# SparkFun_DC-DC_Converter_Breakout.net
KiCad netlist of a schematic drawn in EAGLE
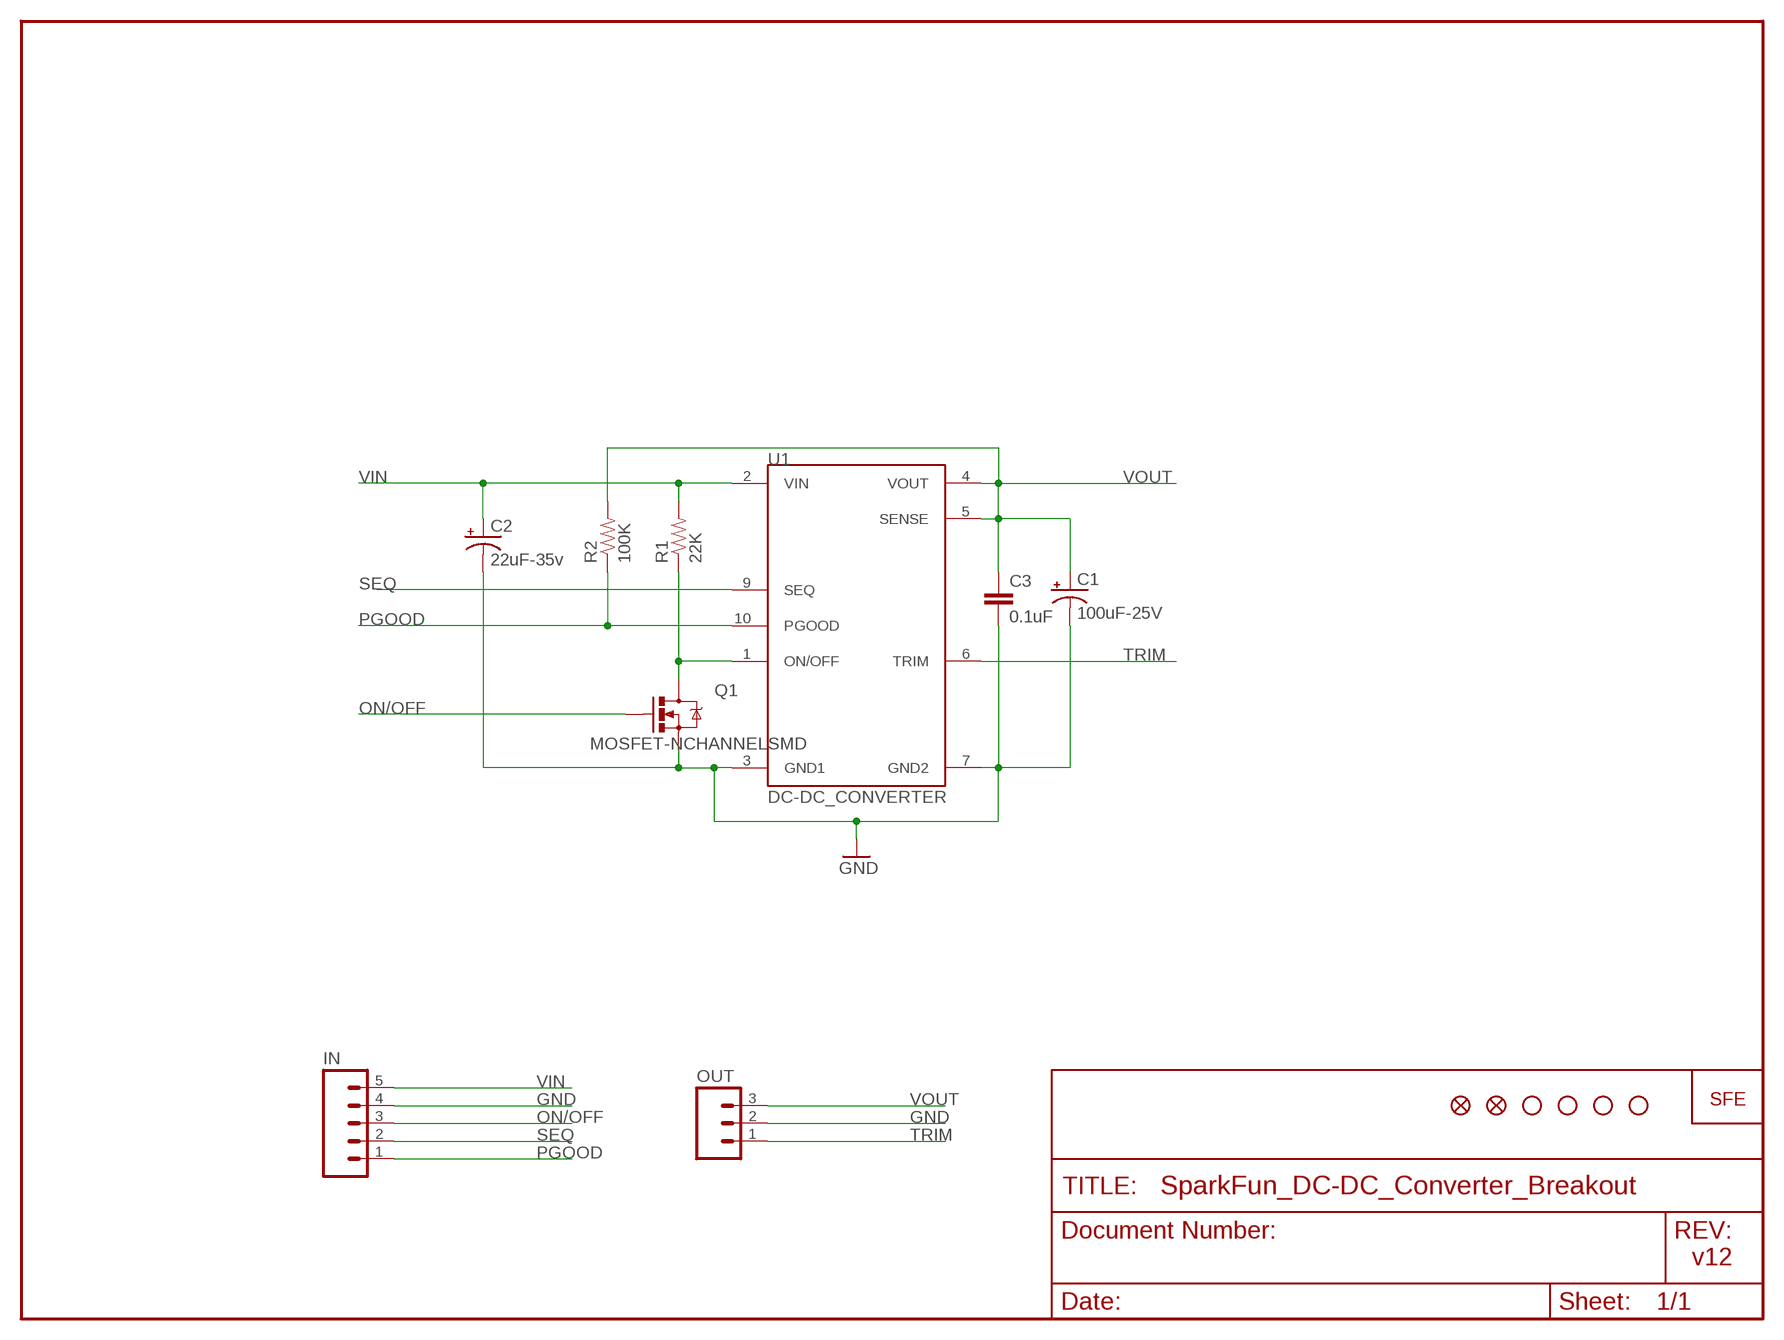
[diagram p0: schematic, sheet 1]

(export (version "E")
  (design (tool "Eeschema 10.0.6"))
  (components
    (comp (ref "C1")
      (value "100uF-25V")
      (footprint "eagle-import:NIPPON_F80")
      (libsource (lib "eagle-import") (part "CAP_POL"))
    )
    (comp (ref "C2")
      (value "22uF-35v")
      (footprint "eagle-import:PANASONIC_C")
      (libsource (lib "eagle-import") (part "CAP_POLC"))
    )
    (comp (ref "C3")
      (value "0.1uF")
      (footprint "eagle-import:0603-CAP")
      (libsource (lib "eagle-import") (part "CAP0603-CAP"))
    )
    (comp (ref "FID1")
      (value "FIDUCIAL1X2")
      (footprint "eagle-import:FIDUCIAL-1X2")
      (libsource (lib "eagle-import") (part "FIDUCIAL1X2"))
    )
    (comp (ref "FID2")
      (value "FIDUCIAL1X2")
      (footprint "eagle-import:FIDUCIAL-1X2")
      (libsource (lib "eagle-import") (part "FIDUCIAL1X2"))
    )
    (comp (ref "IN")
      (value "M05PTH")
      (footprint "eagle-import:1X05")
      (libsource (lib "eagle-import") (part "M05PTH"))
    )
    (comp (ref "OUT")
      (value "M03PTH")
      (footprint "eagle-import:1X03")
      (libsource (lib "eagle-import") (part "M03PTH"))
    )
    (comp (ref "Q1")
      (value "MOSFET-NCHANNELSMD")
      (footprint "eagle-import:SOT23-3")
      (libsource (lib "eagle-import") (part "MOSFET-NCHANNELSMD"))
    )
    (comp (ref "R1")
      (value "22K")
      (footprint "eagle-import:0603-RES")
      (libsource (lib "eagle-import") (part "RESISTOR0603-RES"))
    )
    (comp (ref "R2")
      (value "100K")
      (footprint "eagle-import:0603-RES")
      (libsource (lib "eagle-import") (part "RESISTOR0603-RES"))
    )
    (comp (ref "U$1")
      (value "STAND-OFF")
      (footprint "eagle-import:STAND-OFF")
      (libsource (lib "eagle-import") (part "STAND-OFF"))
    )
    (comp (ref "U$2")
      (value "LOGO-SFENEW")
      (footprint "eagle-import:SFE-NEW-WEBLOGO")
      (libsource (lib "eagle-import") (part "LOGO-SFENEW"))
    )
    (comp (ref "U$3")
      (value "STAND-OFF")
      (footprint "eagle-import:STAND-OFF")
      (libsource (lib "eagle-import") (part "STAND-OFF"))
    )
    (comp (ref "U$4")
      (value "STAND-OFF")
      (footprint "eagle-import:STAND-OFF")
      (libsource (lib "eagle-import") (part "STAND-OFF"))
    )
    (comp (ref "U$5")
      (value "STAND-OFF")
      (footprint "eagle-import:STAND-OFF")
      (libsource (lib "eagle-import") (part "STAND-OFF"))
    )
    (comp (ref "U1")
      (value "DC-DC_CONVERTER")
      (footprint "eagle-import:DC-DC_CONVERTER")
      (libsource (lib "eagle-import") (part "DC-DC_CONVERTER"))
    )
  )
  (nets
    (net (code "1") (name "/ON{slash}OFF") (class "Default")
      (node (ref "IN") (pin "3") (pinfunction "3_3") (pintype "passive"))
      (node (ref "Q1") (pin "1") (pinfunction "G_1") (pintype "passive"))
    )
    (net (code "2") (name "/PGOOD") (class "Default")
      (node (ref "IN") (pin "1") (pinfunction "1_1") (pintype "passive"))
      (node (ref "R2") (pin "1") (pinfunction "1_1") (pintype "passive"))
      (node (ref "U1") (pin "10") (pinfunction "PGOOD_10") (pintype "bidirectional"))
    )
    (net (code "3") (name "/SEQ") (class "Default")
      (node (ref "IN") (pin "2") (pinfunction "2_2") (pintype "passive"))
      (node (ref "U1") (pin "9") (pinfunction "SEQ_9") (pintype "bidirectional"))
    )
    (net (code "4") (name "/TRIM") (class "Default")
      (node (ref "OUT") (pin "1") (pinfunction "1_1") (pintype "passive"))
      (node (ref "U1") (pin "6") (pinfunction "TRIM_6") (pintype "bidirectional"))
    )
    (net (code "5") (name "/VIN") (class "Default")
      (node (ref "C2") (pin "+") (pinfunction "+_+") (pintype "passive"))
      (node (ref "IN") (pin "5") (pinfunction "5_5") (pintype "passive"))
      (node (ref "R1") (pin "2") (pinfunction "2_2") (pintype "passive"))
      (node (ref "U1") (pin "2") (pinfunction "VIN_2") (pintype "bidirectional"))
    )
    (net (code "6") (name "/VOUT") (class "Default")
      (node (ref "C1") (pin "+") (pinfunction "+_+") (pintype "passive"))
      (node (ref "C3") (pin "1") (pinfunction "1_1") (pintype "passive"))
      (node (ref "OUT") (pin "3") (pinfunction "3_3") (pintype "passive"))
      (node (ref "R2") (pin "2") (pinfunction "2_2") (pintype "passive"))
      (node (ref "U1") (pin "4") (pinfunction "VOUT_4") (pintype "bidirectional"))
      (node (ref "U1") (pin "5") (pinfunction "SENSE_5") (pintype "bidirectional"))
    )
    (net (code "7") (name "GND") (class "Default")
      (node (ref "C1") (pin "-") (pinfunction "-_-") (pintype "passive"))
      (node (ref "C2") (pin "-") (pinfunction "-_-") (pintype "passive"))
      (node (ref "C3") (pin "2") (pinfunction "2_2") (pintype "passive"))
      (node (ref "IN") (pin "4") (pinfunction "4_4") (pintype "passive"))
      (node (ref "OUT") (pin "2") (pinfunction "2_2") (pintype "passive"))
      (node (ref "Q1") (pin "2") (pinfunction "S_2") (pintype "passive"))
      (node (ref "U1") (pin "3") (pinfunction "GND1_3") (pintype "bidirectional"))
      (node (ref "U1") (pin "7") (pinfunction "GND2_7") (pintype "bidirectional"))
    )
    (net (code "8") (name "Net-(Q1-D)") (class "Default")
      (node (ref "Q1") (pin "3") (pinfunction "D_3") (pintype "passive"))
      (node (ref "R1") (pin "1") (pinfunction "1_1") (pintype "passive"))
      (node (ref "U1") (pin "1") (pinfunction "ON/OFF_1") (pintype "bidirectional"))
    )
  )
)
